# Converti_Alim.net
KiCad netlist of a schematic drawn in Altium Designer
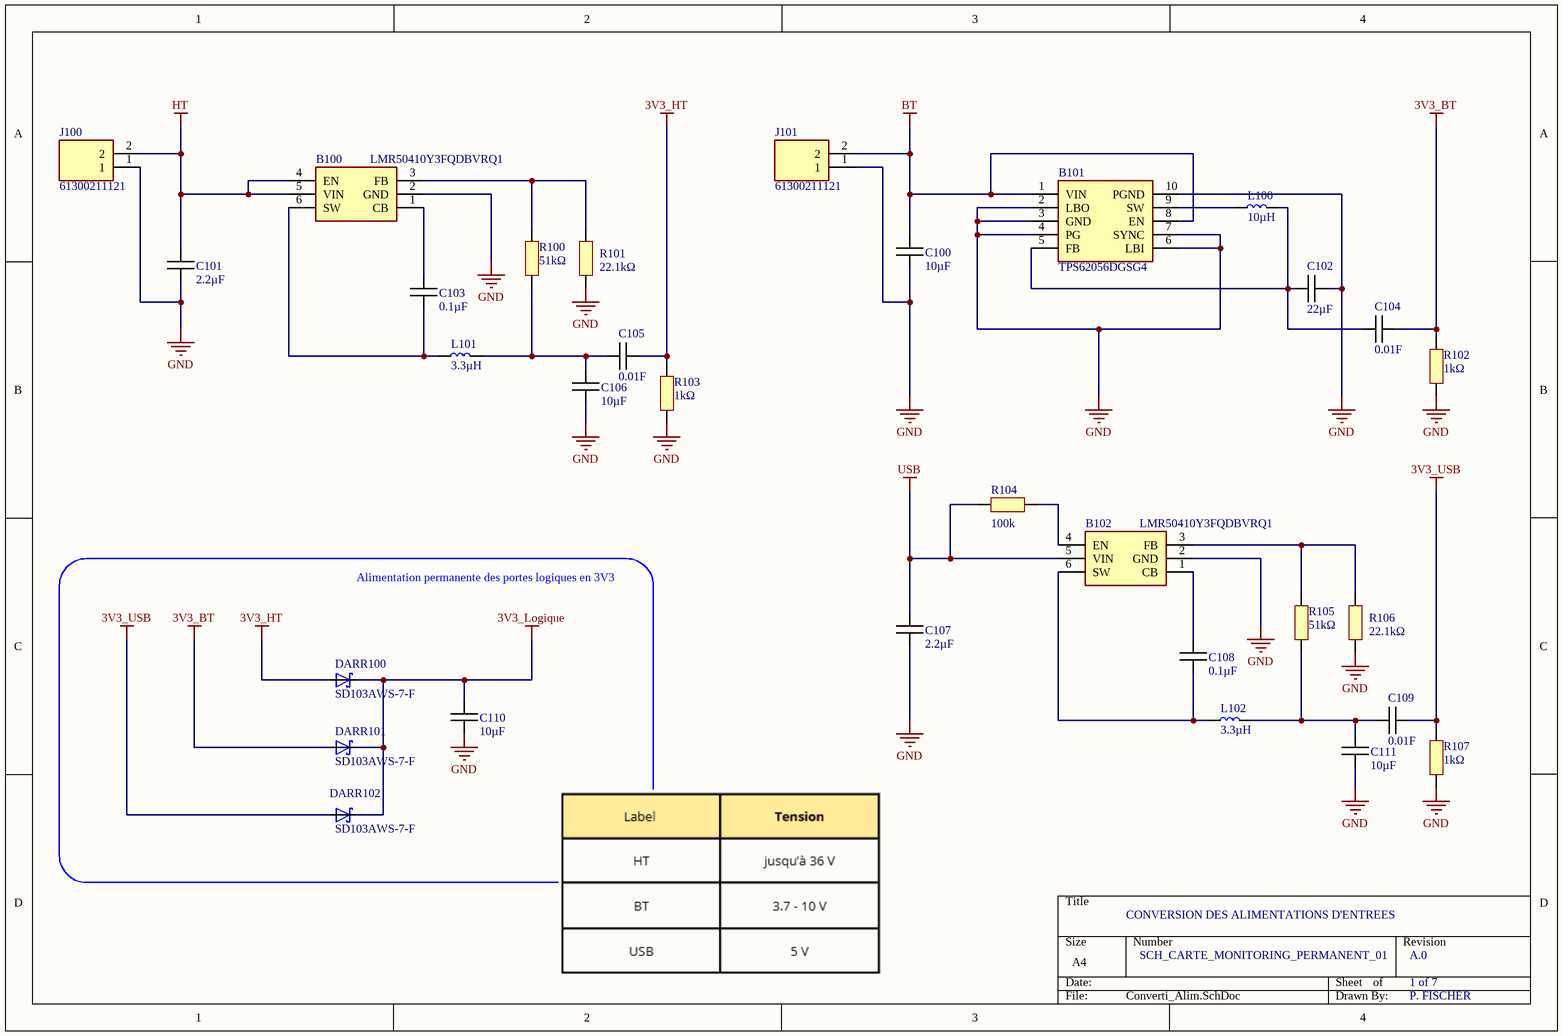
[diagram p0: Converti_Alim.SchDoc]

(export (version "E")
  (design (tool "Eeschema 10.0.6"))
  (components
    (comp (ref "B100")
      (value "LMR50410Y3FQDBVRQ1")
      (footprint "SOT95P280X145-6N")
      (fields (field (name "MOUSER PART NUMBER") "595-R50410Y3FQDBVRQ1"))
      (libsource (lib "SCHLibrary") (part "LMR50410Y3FQDBVRQ1"))
    )
    (comp (ref "B101")
      (value "TPS62056DGSG4")
      (footprint "SOP50P490X110-10N")
      (fields (field (name "MOUSER PART NUMBER") "595-TPS62056DGSG4"))
      (libsource (lib "SCHLibrary") (part "TPS62056DGSG4"))
    )
    (comp (ref "B102")
      (value "LMR50410Y3FQDBVRQ1")
      (footprint "SOT95P280X145-6N")
      (fields (field (name "MOUSER PART NUMBER") "595-R50410Y3FQDBVRQ1"))
      (libsource (lib "SCHLibrary") (part "LMR50410Y3FQDBVRQ1"))
    )
    (comp (ref "C100")
      (value "10µF")
      (footprint "CAPC1005X06N")
      (libsource (lib "SCHLibrary") (part "Capacitor"))
    )
    (comp (ref "C101")
      (value "2.2µF")
      (footprint "CAPC1005X06N")
      (libsource (lib "SCHLibrary") (part "Capacitor"))
    )
    (comp (ref "C102")
      (value "22µF")
      (footprint "CAPC1005X06N")
      (libsource (lib "SCHLibrary") (part "Capacitor"))
    )
    (comp (ref "C103")
      (value "0.1µF")
      (footprint "CAPC1005X06N")
      (libsource (lib "SCHLibrary") (part "Capacitor"))
    )
    (comp (ref "C104")
      (value "0.01F")
      (footprint "CAPC1005X06N")
      (libsource (lib "SCHLibrary") (part "Capacitor"))
    )
    (comp (ref "C105")
      (value "0.01F")
      (footprint "CAPC1005X06N")
      (libsource (lib "SCHLibrary") (part "Capacitor"))
    )
    (comp (ref "C106")
      (value "10µF")
      (footprint "CAPC1005X06N")
      (libsource (lib "SCHLibrary") (part "Capacitor"))
    )
    (comp (ref "C107")
      (value "2.2µF")
      (footprint "CAPC1005X06N")
      (libsource (lib "SCHLibrary") (part "Capacitor"))
    )
    (comp (ref "C108")
      (value "0.1µF")
      (footprint "CAPC1005X06N")
      (libsource (lib "SCHLibrary") (part "Capacitor"))
    )
    (comp (ref "C109")
      (value "0.01F")
      (footprint "CAPC1005X06N")
      (libsource (lib "SCHLibrary") (part "Capacitor"))
    )
    (comp (ref "C110")
      (value "10µF")
      (footprint "CAPC1005X06N")
      (libsource (lib "SCHLibrary") (part "Capacitor"))
    )
    (comp (ref "C111")
      (value "10µF")
      (footprint "CAPC1005X06N")
      (libsource (lib "SCHLibrary") (part "Capacitor"))
    )
    (comp (ref "DARR100")
      (value "SD103AWS-7-F")
      (footprint "SD103AWS-7-F")
      (description "Diode Array 3 Independent Schottky 40V 175mA Surface Mount 6-TSSOP, SC-88, SOT-363")
      (libsource (lib "SCHLibrary") (part "SD103AWS-7-F"))
    )
    (comp (ref "DARR101")
      (value "SD103AWS-7-F")
      (footprint "SD103AWS-7-F")
      (description "Diode Array 3 Independent Schottky 40V 175mA Surface Mount 6-TSSOP, SC-88, SOT-363")
      (libsource (lib "SCHLibrary") (part "SD103AWS-7-F"))
    )
    (comp (ref "DARR102")
      (value "SD103AWS-7-F")
      (footprint "SD103AWS-7-F")
      (description "Diode Array 3 Independent Schottky 40V 175mA Surface Mount 6-TSSOP, SC-88, SOT-363")
      (libsource (lib "SCHLibrary") (part "SD103AWS-7-F"))
    )
    (comp (ref "J100")
      (value "61300211121")
      (footprint "61300211121")
      (description "WURTH ELEKTRONIK - 61300211121 - HEADER, 2.54MM, PIN, THT, VERTICAL, 2WAY")
      (libsource (lib "SCHLibrary") (part "61300211121"))
    )
    (comp (ref "J101")
      (value "61300211121")
      (footprint "61300211121")
      (description "WURTH ELEKTRONIK - 61300211121 - HEADER, 2.54MM, PIN, THT, VERTICAL, 2WAY")
      (libsource (lib "SCHLibrary") (part "61300211121"))
    )
    (comp (ref "L100")
      (value "10µH")
      (footprint "LQPC1005X06N")
      (libsource (lib "SCHLibrary") (part "Bobine"))
    )
    (comp (ref "L101")
      (value "3.3µH")
      (footprint "LQPC1005X06N")
      (libsource (lib "SCHLibrary") (part "Bobine"))
    )
    (comp (ref "L102")
      (value "3.3µH")
      (footprint "LQPC1005X06N")
      (libsource (lib "SCHLibrary") (part "Bobine"))
    )
    (comp (ref "R100")
      (value "51kΩ")
      (footprint "RESC1005X06N")
      (libsource (lib "SCHLibrary") (part "Resistor"))
    )
    (comp (ref "R101")
      (value "22.1kΩ")
      (footprint "RESC1005X06N")
      (libsource (lib "SCHLibrary") (part "Resistor"))
    )
    (comp (ref "R102")
      (value "1kΩ")
      (footprint "RESC1005X06N")
      (libsource (lib "SCHLibrary") (part "Resistor"))
    )
    (comp (ref "R103")
      (value "1kΩ")
      (footprint "RESC1005X06N")
      (libsource (lib "SCHLibrary") (part "Resistor"))
    )
    (comp (ref "R104") (value "100k") (footprint "RESC1005X06N") (libsource (lib "") (part "Resistor_1")))
    (comp (ref "R105")
      (value "51kΩ")
      (footprint "RESC1005X06N")
      (libsource (lib "SCHLibrary") (part "Resistor"))
    )
    (comp (ref "R106")
      (value "22.1kΩ")
      (footprint "RESC1005X06N")
      (libsource (lib "SCHLibrary") (part "Resistor"))
    )
    (comp (ref "R107")
      (value "1kΩ")
      (footprint "RESC1005X06N")
      (libsource (lib "SCHLibrary") (part "Resistor"))
    )
  )
  (nets
    (net (code "1") (name "3V3_BT") (class "Default")
      (node (ref "C104") (pin "2") (pinfunction "2_2") (pintype "passive"))
      (node (ref "DARR101") (pin "2") (pinfunction "A_2") (pintype "passive"))
      (node (ref "R102") (pin "2") (pinfunction "2_2") (pintype "passive"))
    )
    (net (code "2") (name "3V3_HT") (class "Default")
      (node (ref "C105") (pin "2") (pinfunction "2_2") (pintype "passive"))
      (node (ref "DARR100") (pin "2") (pinfunction "A_2") (pintype "passive"))
      (node (ref "R103") (pin "2") (pinfunction "2_2") (pintype "passive"))
    )
    (net (code "3") (name "3V3_Logique") (class "Default")
      (node (ref "C110") (pin "1") (pinfunction "1_1") (pintype "passive"))
      (node (ref "DARR100") (pin "1") (pinfunction "C_1") (pintype "passive"))
      (node (ref "DARR101") (pin "1") (pinfunction "C_1") (pintype "passive"))
      (node (ref "DARR102") (pin "1") (pinfunction "C_1") (pintype "passive"))
    )
    (net (code "4") (name "3V3_USB") (class "Default")
      (node (ref "C109") (pin "2") (pinfunction "2_2") (pintype "passive"))
      (node (ref "DARR102") (pin "2") (pinfunction "A_2") (pintype "passive"))
      (node (ref "R107") (pin "2") (pinfunction "2_2") (pintype "passive"))
    )
    (net (code "5") (name "BT") (class "Default")
      (node (ref "B101") (pin "1") (pinfunction "VIN_1") (pintype "passive"))
      (node (ref "B101") (pin "8") (pinfunction "EN_8") (pintype "passive"))
      (node (ref "C100") (pin "1") (pinfunction "1_1") (pintype "passive"))
      (node (ref "J101") (pin "2") (pinfunction "2_2") (pintype "passive"))
    )
    (net (code "6") (name "GND") (class "Default")
      (node (ref "B100") (pin "2") (pinfunction "GND_2") (pintype "passive"))
      (node (ref "B101") (pin "10") (pinfunction "PGND_10") (pintype "passive"))
      (node (ref "B101") (pin "2") (pinfunction "LBO_2") (pintype "passive"))
      (node (ref "B101") (pin "3") (pinfunction "GND_3") (pintype "passive"))
      (node (ref "B101") (pin "4") (pinfunction "PG_4") (pintype "passive"))
      (node (ref "B101") (pin "6") (pinfunction "LBI_6") (pintype "passive"))
      (node (ref "B101") (pin "7") (pinfunction "SYNC_7") (pintype "passive"))
      (node (ref "B102") (pin "2") (pinfunction "GND_2") (pintype "passive"))
      (node (ref "C100") (pin "2") (pinfunction "2_2") (pintype "passive"))
      (node (ref "C101") (pin "2") (pinfunction "2_2") (pintype "passive"))
      (node (ref "C102") (pin "2") (pinfunction "2_2") (pintype "passive"))
      (node (ref "C106") (pin "2") (pinfunction "2_2") (pintype "passive"))
      (node (ref "C107") (pin "2") (pinfunction "2_2") (pintype "passive"))
      (node (ref "C110") (pin "2") (pinfunction "2_2") (pintype "passive"))
      (node (ref "C111") (pin "2") (pinfunction "2_2") (pintype "passive"))
      (node (ref "J100") (pin "1") (pinfunction "1_1") (pintype "passive"))
      (node (ref "J101") (pin "1") (pinfunction "1_1") (pintype "passive"))
      (node (ref "R101") (pin "1") (pinfunction "1_1") (pintype "passive"))
      (node (ref "R102") (pin "1") (pinfunction "1_1") (pintype "passive"))
      (node (ref "R103") (pin "1") (pinfunction "1_1") (pintype "passive"))
      (node (ref "R106") (pin "1") (pinfunction "1_1") (pintype "passive"))
      (node (ref "R107") (pin "1") (pinfunction "1_1") (pintype "passive"))
    )
    (net (code "7") (name "HT") (class "Default")
      (node (ref "B100") (pin "4") (pinfunction "EN_4") (pintype "passive"))
      (node (ref "B100") (pin "5") (pinfunction "VIN_5") (pintype "passive"))
      (node (ref "C101") (pin "1") (pinfunction "1_1") (pintype "passive"))
      (node (ref "J100") (pin "2") (pinfunction "2_2") (pintype "passive"))
    )
    (net (code "8") (name "Net-(B100-CB)") (class "Default")
      (node (ref "B100") (pin "1") (pinfunction "CB_1") (pintype "passive"))
      (node (ref "C103") (pin "1") (pinfunction "1_1") (pintype "passive"))
    )
    (net (code "9") (name "Net-(B100-FB)") (class "Default")
      (node (ref "B100") (pin "3") (pinfunction "FB_3") (pintype "passive"))
      (node (ref "R100") (pin "2") (pinfunction "2_2") (pintype "passive"))
      (node (ref "R101") (pin "2") (pinfunction "2_2") (pintype "passive"))
    )
    (net (code "10") (name "Net-(B100-SW)") (class "Default")
      (node (ref "B100") (pin "6") (pinfunction "SW_6") (pintype "passive"))
      (node (ref "C103") (pin "2") (pinfunction "2_2") (pintype "passive"))
      (node (ref "L101") (pin "1") (pinfunction "1_1") (pintype "passive"))
    )
    (net (code "11") (name "Net-(B101-FB)") (class "Default")
      (node (ref "B101") (pin "5") (pinfunction "FB_5") (pintype "passive"))
      (node (ref "C102") (pin "1") (pinfunction "1_1") (pintype "passive"))
      (node (ref "C104") (pin "1") (pinfunction "1_1") (pintype "passive"))
      (node (ref "L100") (pin "2") (pinfunction "2_2") (pintype "passive"))
    )
    (net (code "12") (name "Net-(B101-SW)") (class "Default")
      (node (ref "B101") (pin "9") (pinfunction "SW_9") (pintype "passive"))
      (node (ref "L100") (pin "1") (pinfunction "1_1") (pintype "passive"))
    )
    (net (code "13") (name "Net-(B102-CB)") (class "Default")
      (node (ref "B102") (pin "1") (pinfunction "CB_1") (pintype "passive"))
      (node (ref "C108") (pin "1") (pinfunction "1_1") (pintype "passive"))
    )
    (net (code "14") (name "Net-(B102-EN)") (class "Default")
      (node (ref "B102") (pin "4") (pinfunction "EN_4") (pintype "passive"))
      (node (ref "R104") (pin "2") (pinfunction "2_2") (pintype "passive"))
    )
    (net (code "15") (name "Net-(B102-FB)") (class "Default")
      (node (ref "B102") (pin "3") (pinfunction "FB_3") (pintype "passive"))
      (node (ref "R105") (pin "2") (pinfunction "2_2") (pintype "passive"))
      (node (ref "R106") (pin "2") (pinfunction "2_2") (pintype "passive"))
    )
    (net (code "16") (name "Net-(B102-SW)") (class "Default")
      (node (ref "B102") (pin "6") (pinfunction "SW_6") (pintype "passive"))
      (node (ref "C108") (pin "2") (pinfunction "2_2") (pintype "passive"))
      (node (ref "L102") (pin "1") (pinfunction "1_1") (pintype "passive"))
    )
    (net (code "17") (name "Net-(C105-Pad1)") (class "Default")
      (node (ref "C105") (pin "1") (pinfunction "1_1") (pintype "passive"))
      (node (ref "C106") (pin "1") (pinfunction "1_1") (pintype "passive"))
      (node (ref "L101") (pin "2") (pinfunction "2_2") (pintype "passive"))
      (node (ref "R100") (pin "1") (pinfunction "1_1") (pintype "passive"))
    )
    (net (code "18") (name "Net-(C109-Pad1)") (class "Default")
      (node (ref "C109") (pin "1") (pinfunction "1_1") (pintype "passive"))
      (node (ref "C111") (pin "1") (pinfunction "1_1") (pintype "passive"))
      (node (ref "L102") (pin "2") (pinfunction "2_2") (pintype "passive"))
      (node (ref "R105") (pin "1") (pinfunction "1_1") (pintype "passive"))
    )
    (net (code "19") (name "USB") (class "Default")
      (node (ref "B102") (pin "5") (pinfunction "VIN_5") (pintype "passive"))
      (node (ref "C107") (pin "1") (pinfunction "1_1") (pintype "passive"))
      (node (ref "R104") (pin "1") (pinfunction "1_1") (pintype "passive"))
    )
  )
)
